# nucleo_breakout.net
KiCad netlist of a schematic drawn in Altium Designer
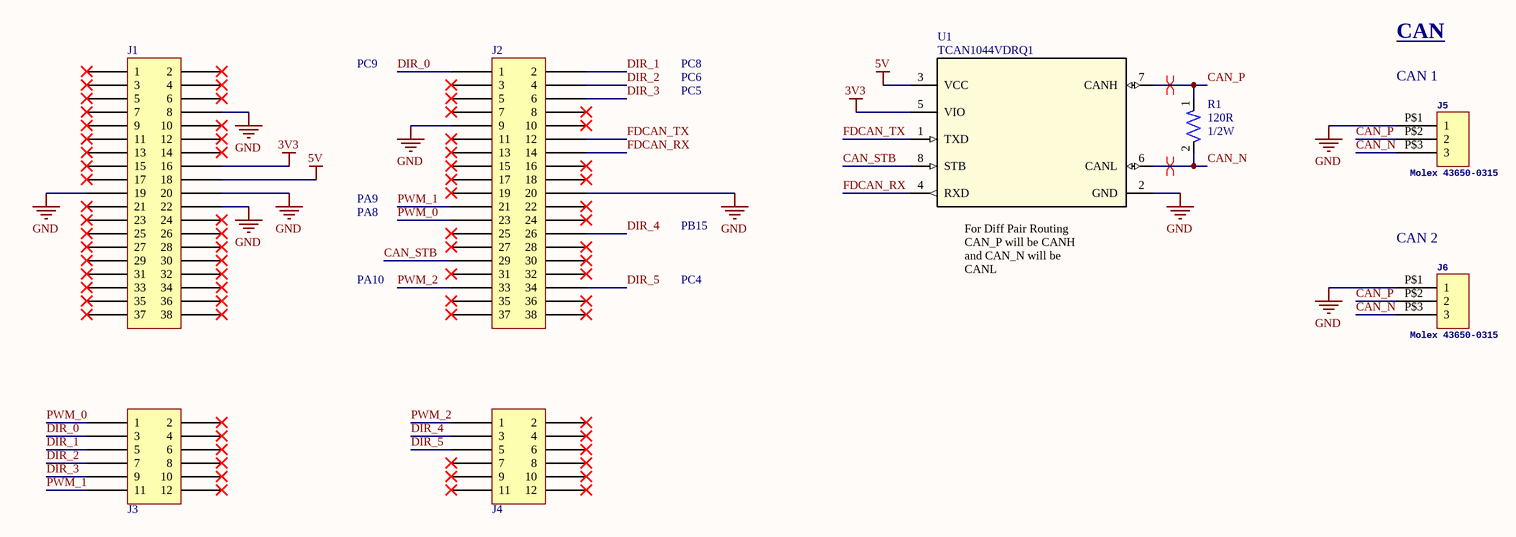
[diagram p0: nucleo_breakout.SchDoc]

(export (version "E")
  (design (tool "Eeschema 10.0.6"))
  (components
    (comp (ref "J1")
      (value "PPPC192LFBN-RC")
      (footprint "CONN-38POS_01")
      (libsource (lib "temp_lib") (part "CONN-38POS-01"))
    )
    (comp (ref "J2")
      (value "PPPC192LFBN-RC")
      (footprint "CONN-38POS_01")
      (libsource (lib "temp_lib") (part "CONN-38POS-01"))
    )
    (comp (ref "J3")
      (value "PPTC062LFBN-RC")
      (footprint "CONN-6POS_01")
      (description "12 Position Header Connector 0.100\" (2.54mm) Through Hole Tin")
      (libsource (lib "temp_lib") (part "CONN-12POS-01"))
    )
    (comp (ref "J4")
      (value "PPTC062LFBN-RC")
      (footprint "CONN-6POS_01")
      (description "12 Position Header Connector 0.100\" (2.54mm) Through Hole Tin")
      (libsource (lib "temp_lib") (part "CONN-12POS-01"))
    )
    (comp (ref "J5")
      (value "Molex 43650-0315")
      (footprint "43650-0315")
      (libsource (lib "Molex Microfit") (part "Micro-Fit Molex 3 Pin Vertical"))
    )
    (comp (ref "J6")
      (value "Molex 43650-0315")
      (footprint "43650-0315")
      (libsource (lib "Molex Microfit") (part "Micro-Fit Molex 3 Pin Vertical"))
    )
    (comp (ref "R1")
      (value "RC1210FR-07120RL")
      (footprint "RES-1210")
      (description "RES 120 OHM 1% 1/2W 1210")
      (fields
        (field (name "TOLERANCE") "1%")
        (field (name "POWER") "1/2W")
        (field (name "RESISTANCE") "120R")
      )
      (libsource (lib "JLC_25") (part "RES-120-0001"))
    )
    (comp (ref "U1")
      (value "TCAN1044VDRQ1")
      (footprint "IC-8SOIC")
      (description "IC TRANSCEIVER 1/1 8SOIC")
      (libsource (lib "JLC_25") (part "IC-CAN-0001"))
    )
  )
  (nets
    (net (code "1") (name "/CAN_N") (class "Default")
      (node (ref "J5") (pin "P$3") (pinfunction "3_P$3") (pintype "passive"))
      (node (ref "J6") (pin "P$3") (pinfunction "3_P$3") (pintype "passive"))
      (node (ref "R1") (pin "2") (pinfunction "2_2") (pintype "passive"))
      (node (ref "U1") (pin "6") (pinfunction "CANL_6") (pintype "bidirectional"))
    )
    (net (code "2") (name "/CAN_P") (class "Default")
      (node (ref "J5") (pin "P$2") (pinfunction "2_P$2") (pintype "passive"))
      (node (ref "J6") (pin "P$2") (pinfunction "2_P$2") (pintype "passive"))
      (node (ref "R1") (pin "1") (pinfunction "1_1") (pintype "passive"))
      (node (ref "U1") (pin "7") (pinfunction "CANH_7") (pintype "bidirectional"))
    )
    (net (code "3") (name "/CAN_STB") (class "Default")
      (node (ref "J2") (pin "29") (pinfunction "29_29") (pintype "passive"))
      (node (ref "U1") (pin "8") (pinfunction "STB_8") (pintype "input"))
    )
    (net (code "4") (name "/DIR_0") (class "Default")
      (node (ref "J2") (pin "1") (pinfunction "1_1") (pintype "passive"))
      (node (ref "J3") (pin "3") (pinfunction "3_3") (pintype "passive"))
    )
    (net (code "5") (name "/DIR_1") (class "Default")
      (node (ref "J2") (pin "2") (pinfunction "2_2") (pintype "passive"))
      (node (ref "J3") (pin "5") (pinfunction "5_5") (pintype "passive"))
    )
    (net (code "6") (name "/DIR_2") (class "Default")
      (node (ref "J2") (pin "4") (pinfunction "4_4") (pintype "passive"))
      (node (ref "J3") (pin "7") (pinfunction "7_7") (pintype "passive"))
    )
    (net (code "7") (name "/DIR_3") (class "Default")
      (node (ref "J2") (pin "6") (pinfunction "6_6") (pintype "passive"))
      (node (ref "J3") (pin "9") (pinfunction "9_9") (pintype "passive"))
    )
    (net (code "8") (name "/DIR_4") (class "Default")
      (node (ref "J2") (pin "26") (pinfunction "26_26") (pintype "passive"))
      (node (ref "J4") (pin "3") (pinfunction "3_3") (pintype "passive"))
    )
    (net (code "9") (name "/DIR_5") (class "Default")
      (node (ref "J2") (pin "34") (pinfunction "34_34") (pintype "passive"))
      (node (ref "J4") (pin "5") (pinfunction "5_5") (pintype "passive"))
    )
    (net (code "10") (name "/FDCAN_RX") (class "Default")
      (node (ref "J2") (pin "14") (pinfunction "14_14") (pintype "passive"))
      (node (ref "U1") (pin "4") (pinfunction "RXD_4") (pintype "output"))
    )
    (net (code "11") (name "/FDCAN_TX") (class "Default")
      (node (ref "J2") (pin "12") (pinfunction "12_12") (pintype "passive"))
      (node (ref "U1") (pin "1") (pinfunction "TXD_1") (pintype "input"))
    )
    (net (code "12") (name "/PWM_0") (class "Default")
      (node (ref "J2") (pin "23") (pinfunction "23_23") (pintype "passive"))
      (node (ref "J3") (pin "1") (pinfunction "1_1") (pintype "passive"))
    )
    (net (code "13") (name "/PWM_1") (class "Default")
      (node (ref "J2") (pin "21") (pinfunction "21_21") (pintype "passive"))
      (node (ref "J3") (pin "11") (pinfunction "11_11") (pintype "passive"))
    )
    (net (code "14") (name "/PWM_2") (class "Default")
      (node (ref "J2") (pin "33") (pinfunction "33_33") (pintype "passive"))
      (node (ref "J4") (pin "1") (pinfunction "1_1") (pintype "passive"))
    )
    (net (code "15") (name "3V3") (class "Default")
      (node (ref "J1") (pin "16") (pinfunction "16_16") (pintype "passive"))
      (node (ref "U1") (pin "5") (pinfunction "VIO_5") (pintype "power_in"))
    )
    (net (code "16") (name "5V") (class "Default")
      (node (ref "J1") (pin "18") (pinfunction "18_18") (pintype "passive"))
      (node (ref "U1") (pin "3") (pinfunction "VCC_3") (pintype "power_in"))
    )
    (net (code "17") (name "GND") (class "Default")
      (node (ref "J1") (pin "19") (pinfunction "19_19") (pintype "passive"))
      (node (ref "J1") (pin "20") (pinfunction "20_20") (pintype "passive"))
      (node (ref "J1") (pin "22") (pinfunction "22_22") (pintype "passive"))
      (node (ref "J1") (pin "8") (pinfunction "8_8") (pintype "passive"))
      (node (ref "J2") (pin "20") (pinfunction "20_20") (pintype "passive"))
      (node (ref "J2") (pin "9") (pinfunction "9_9") (pintype "passive"))
      (node (ref "J5") (pin "P$1") (pinfunction "1_P$1") (pintype "passive"))
      (node (ref "J6") (pin "P$1") (pinfunction "1_P$1") (pintype "passive"))
      (node (ref "U1") (pin "2") (pinfunction "GND_2") (pintype "power_in"))
    )
    (net (code "18") (name "unconnected-(J1-Pad1)") (class "Default")
      (node (ref "J1") (pin "1") (pinfunction "1_1") (pintype "passive+no_connect"))
    )
    (net (code "19") (name "unconnected-(J1-Pad2)") (class "Default")
      (node (ref "J1") (pin "2") (pinfunction "2_2") (pintype "passive+no_connect"))
    )
    (net (code "20") (name "unconnected-(J1-Pad3)") (class "Default")
      (node (ref "J1") (pin "3") (pinfunction "3_3") (pintype "passive+no_connect"))
    )
    (net (code "21") (name "unconnected-(J1-Pad4)") (class "Default")
      (node (ref "J1") (pin "4") (pinfunction "4_4") (pintype "passive+no_connect"))
    )
    (net (code "22") (name "unconnected-(J1-Pad5)") (class "Default")
      (node (ref "J1") (pin "5") (pinfunction "5_5") (pintype "passive+no_connect"))
    )
    (net (code "23") (name "unconnected-(J1-Pad6)") (class "Default")
      (node (ref "J1") (pin "6") (pinfunction "6_6") (pintype "passive+no_connect"))
    )
    (net (code "24") (name "unconnected-(J1-Pad7)") (class "Default")
      (node (ref "J1") (pin "7") (pinfunction "7_7") (pintype "passive+no_connect"))
    )
    (net (code "25") (name "unconnected-(J1-Pad9)") (class "Default")
      (node (ref "J1") (pin "9") (pinfunction "9_9") (pintype "passive+no_connect"))
    )
    (net (code "26") (name "unconnected-(J1-Pad10)") (class "Default")
      (node (ref "J1") (pin "10") (pinfunction "10_10") (pintype "passive+no_connect"))
    )
    (net (code "27") (name "unconnected-(J1-Pad11)") (class "Default")
      (node (ref "J1") (pin "11") (pinfunction "11_11") (pintype "passive+no_connect"))
    )
    (net (code "28") (name "unconnected-(J1-Pad12)") (class "Default")
      (node (ref "J1") (pin "12") (pinfunction "12_12") (pintype "passive+no_connect"))
    )
    (net (code "29") (name "unconnected-(J1-Pad13)") (class "Default")
      (node (ref "J1") (pin "13") (pinfunction "13_13") (pintype "passive+no_connect"))
    )
    (net (code "30") (name "unconnected-(J1-Pad14)") (class "Default")
      (node (ref "J1") (pin "14") (pinfunction "14_14") (pintype "passive+no_connect"))
    )
    (net (code "31") (name "unconnected-(J1-Pad15)") (class "Default")
      (node (ref "J1") (pin "15") (pinfunction "15_15") (pintype "passive+no_connect"))
    )
    (net (code "32") (name "unconnected-(J1-Pad17)") (class "Default")
      (node (ref "J1") (pin "17") (pinfunction "17_17") (pintype "passive+no_connect"))
    )
    (net (code "33") (name "unconnected-(J1-Pad21)") (class "Default")
      (node (ref "J1") (pin "21") (pinfunction "21_21") (pintype "passive+no_connect"))
    )
    (net (code "34") (name "unconnected-(J1-Pad23)") (class "Default")
      (node (ref "J1") (pin "23") (pinfunction "23_23") (pintype "passive+no_connect"))
    )
    (net (code "35") (name "unconnected-(J1-Pad24)") (class "Default")
      (node (ref "J1") (pin "24") (pinfunction "24_24") (pintype "passive+no_connect"))
    )
    (net (code "36") (name "unconnected-(J1-Pad25)") (class "Default")
      (node (ref "J1") (pin "25") (pinfunction "25_25") (pintype "passive+no_connect"))
    )
    (net (code "37") (name "unconnected-(J1-Pad26)") (class "Default")
      (node (ref "J1") (pin "26") (pinfunction "26_26") (pintype "passive+no_connect"))
    )
    (net (code "38") (name "unconnected-(J1-Pad27)") (class "Default")
      (node (ref "J1") (pin "27") (pinfunction "27_27") (pintype "passive+no_connect"))
    )
    (net (code "39") (name "unconnected-(J1-Pad28)") (class "Default")
      (node (ref "J1") (pin "28") (pinfunction "28_28") (pintype "passive+no_connect"))
    )
    (net (code "40") (name "unconnected-(J1-Pad29)") (class "Default")
      (node (ref "J1") (pin "29") (pinfunction "29_29") (pintype "passive+no_connect"))
    )
    (net (code "41") (name "unconnected-(J1-Pad30)") (class "Default")
      (node (ref "J1") (pin "30") (pinfunction "30_30") (pintype "passive+no_connect"))
    )
    (net (code "42") (name "unconnected-(J1-Pad31)") (class "Default")
      (node (ref "J1") (pin "31") (pinfunction "31_31") (pintype "passive+no_connect"))
    )
    (net (code "43") (name "unconnected-(J1-Pad32)") (class "Default")
      (node (ref "J1") (pin "32") (pinfunction "32_32") (pintype "passive+no_connect"))
    )
    (net (code "44") (name "unconnected-(J1-Pad33)") (class "Default")
      (node (ref "J1") (pin "33") (pinfunction "33_33") (pintype "passive+no_connect"))
    )
    (net (code "45") (name "unconnected-(J1-Pad34)") (class "Default")
      (node (ref "J1") (pin "34") (pinfunction "34_34") (pintype "passive+no_connect"))
    )
    (net (code "46") (name "unconnected-(J1-Pad35)") (class "Default")
      (node (ref "J1") (pin "35") (pinfunction "35_35") (pintype "passive+no_connect"))
    )
    (net (code "47") (name "unconnected-(J1-Pad36)") (class "Default")
      (node (ref "J1") (pin "36") (pinfunction "36_36") (pintype "passive+no_connect"))
    )
    (net (code "48") (name "unconnected-(J1-Pad37)") (class "Default")
      (node (ref "J1") (pin "37") (pinfunction "37_37") (pintype "passive+no_connect"))
    )
    (net (code "49") (name "unconnected-(J1-Pad38)") (class "Default")
      (node (ref "J1") (pin "38") (pinfunction "38_38") (pintype "passive+no_connect"))
    )
    (net (code "50") (name "unconnected-(J2-Pad3)") (class "Default")
      (node (ref "J2") (pin "3") (pinfunction "3_3") (pintype "passive+no_connect"))
    )
    (net (code "51") (name "unconnected-(J2-Pad5)") (class "Default")
      (node (ref "J2") (pin "5") (pinfunction "5_5") (pintype "passive+no_connect"))
    )
    (net (code "52") (name "unconnected-(J2-Pad7)") (class "Default")
      (node (ref "J2") (pin "7") (pinfunction "7_7") (pintype "passive+no_connect"))
    )
    (net (code "53") (name "unconnected-(J2-Pad8)") (class "Default")
      (node (ref "J2") (pin "8") (pinfunction "8_8") (pintype "passive+no_connect"))
    )
    (net (code "54") (name "unconnected-(J2-Pad10)") (class "Default")
      (node (ref "J2") (pin "10") (pinfunction "10_10") (pintype "passive+no_connect"))
    )
    (net (code "55") (name "unconnected-(J2-Pad11)") (class "Default")
      (node (ref "J2") (pin "11") (pinfunction "11_11") (pintype "passive+no_connect"))
    )
    (net (code "56") (name "unconnected-(J2-Pad13)") (class "Default")
      (node (ref "J2") (pin "13") (pinfunction "13_13") (pintype "passive+no_connect"))
    )
    (net (code "57") (name "unconnected-(J2-Pad15)") (class "Default")
      (node (ref "J2") (pin "15") (pinfunction "15_15") (pintype "passive+no_connect"))
    )
    (net (code "58") (name "unconnected-(J2-Pad16)") (class "Default")
      (node (ref "J2") (pin "16") (pinfunction "16_16") (pintype "passive+no_connect"))
    )
    (net (code "59") (name "unconnected-(J2-Pad17)") (class "Default")
      (node (ref "J2") (pin "17") (pinfunction "17_17") (pintype "passive+no_connect"))
    )
    (net (code "60") (name "unconnected-(J2-Pad18)") (class "Default")
      (node (ref "J2") (pin "18") (pinfunction "18_18") (pintype "passive+no_connect"))
    )
    (net (code "61") (name "unconnected-(J2-Pad19)") (class "Default")
      (node (ref "J2") (pin "19") (pinfunction "19_19") (pintype "passive+no_connect"))
    )
    (net (code "62") (name "unconnected-(J2-Pad22)") (class "Default")
      (node (ref "J2") (pin "22") (pinfunction "22_22") (pintype "passive+no_connect"))
    )
    (net (code "63") (name "unconnected-(J2-Pad24)") (class "Default")
      (node (ref "J2") (pin "24") (pinfunction "24_24") (pintype "passive+no_connect"))
    )
    (net (code "64") (name "unconnected-(J2-Pad25)") (class "Default")
      (node (ref "J2") (pin "25") (pinfunction "25_25") (pintype "passive+no_connect"))
    )
    (net (code "65") (name "unconnected-(J2-Pad27)") (class "Default")
      (node (ref "J2") (pin "27") (pinfunction "27_27") (pintype "passive+no_connect"))
    )
    (net (code "66") (name "unconnected-(J2-Pad28)") (class "Default")
      (node (ref "J2") (pin "28") (pinfunction "28_28") (pintype "passive+no_connect"))
    )
    (net (code "67") (name "unconnected-(J2-Pad30)") (class "Default")
      (node (ref "J2") (pin "30") (pinfunction "30_30") (pintype "passive+no_connect"))
    )
    (net (code "68") (name "unconnected-(J2-Pad31)") (class "Default")
      (node (ref "J2") (pin "31") (pinfunction "31_31") (pintype "passive+no_connect"))
    )
    (net (code "69") (name "unconnected-(J2-Pad32)") (class "Default")
      (node (ref "J2") (pin "32") (pinfunction "32_32") (pintype "passive+no_connect"))
    )
    (net (code "70") (name "unconnected-(J2-Pad35)") (class "Default")
      (node (ref "J2") (pin "35") (pinfunction "35_35") (pintype "passive+no_connect"))
    )
    (net (code "71") (name "unconnected-(J2-Pad36)") (class "Default")
      (node (ref "J2") (pin "36") (pinfunction "36_36") (pintype "passive+no_connect"))
    )
    (net (code "72") (name "unconnected-(J2-Pad37)") (class "Default")
      (node (ref "J2") (pin "37") (pinfunction "37_37") (pintype "passive+no_connect"))
    )
    (net (code "73") (name "unconnected-(J2-Pad38)") (class "Default")
      (node (ref "J2") (pin "38") (pinfunction "38_38") (pintype "passive+no_connect"))
    )
    (net (code "74") (name "unconnected-(J3-Pad2)") (class "Default")
      (node (ref "J3") (pin "2") (pinfunction "2_2") (pintype "passive+no_connect"))
    )
    (net (code "75") (name "unconnected-(J3-Pad4)") (class "Default")
      (node (ref "J3") (pin "4") (pinfunction "4_4") (pintype "passive+no_connect"))
    )
    (net (code "76") (name "unconnected-(J3-Pad6)") (class "Default")
      (node (ref "J3") (pin "6") (pinfunction "6_6") (pintype "passive+no_connect"))
    )
    (net (code "77") (name "unconnected-(J3-Pad8)") (class "Default")
      (node (ref "J3") (pin "8") (pinfunction "8_8") (pintype "passive+no_connect"))
    )
    (net (code "78") (name "unconnected-(J3-Pad10)") (class "Default")
      (node (ref "J3") (pin "10") (pinfunction "10_10") (pintype "passive+no_connect"))
    )
    (net (code "79") (name "unconnected-(J3-Pad12)") (class "Default")
      (node (ref "J3") (pin "12") (pinfunction "12_12") (pintype "passive+no_connect"))
    )
    (net (code "80") (name "unconnected-(J4-Pad2)") (class "Default")
      (node (ref "J4") (pin "2") (pinfunction "2_2") (pintype "passive+no_connect"))
    )
    (net (code "81") (name "unconnected-(J4-Pad4)") (class "Default")
      (node (ref "J4") (pin "4") (pinfunction "4_4") (pintype "passive+no_connect"))
    )
    (net (code "82") (name "unconnected-(J4-Pad6)") (class "Default")
      (node (ref "J4") (pin "6") (pinfunction "6_6") (pintype "passive+no_connect"))
    )
    (net (code "83") (name "unconnected-(J4-Pad7)") (class "Default")
      (node (ref "J4") (pin "7") (pinfunction "7_7") (pintype "passive+no_connect"))
    )
    (net (code "84") (name "unconnected-(J4-Pad8)") (class "Default")
      (node (ref "J4") (pin "8") (pinfunction "8_8") (pintype "passive+no_connect"))
    )
    (net (code "85") (name "unconnected-(J4-Pad9)") (class "Default")
      (node (ref "J4") (pin "9") (pinfunction "9_9") (pintype "passive+no_connect"))
    )
    (net (code "86") (name "unconnected-(J4-Pad10)") (class "Default")
      (node (ref "J4") (pin "10") (pinfunction "10_10") (pintype "passive+no_connect"))
    )
    (net (code "87") (name "unconnected-(J4-Pad11)") (class "Default")
      (node (ref "J4") (pin "11") (pinfunction "11_11") (pintype "passive+no_connect"))
    )
    (net (code "88") (name "unconnected-(J4-Pad12)") (class "Default")
      (node (ref "J4") (pin "12") (pinfunction "12_12") (pintype "passive+no_connect"))
    )
  )
)
